# PCB_0014.net
KiCad netlist of a schematic drawn in EAGLE
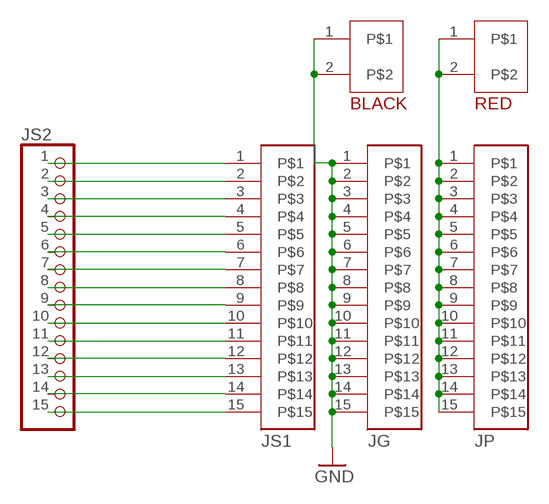
[diagram p0: schematic, sheet 1]

(export (version "E")
  (design (tool "Eeschema 10.0.6"))
  (components
    (comp (ref "BLACK")
      (value "SCREWTERMINAL_2PIN")
      (footprint "eagle-import:DB125-3.5_3.81")
      (libsource (lib "eagle-import") (part "SCREWTERMINAL_2PIN"))
    )
    (comp (ref "JG")
      (value "HEADER_15X1")
      (footprint "eagle-import:HDRV15W64P254_1X15_3810X254X838B")
      (libsource (lib "eagle-import") (part "HEADER_15X1"))
    )
    (comp (ref "JP")
      (value "HEADER_15X1")
      (footprint "eagle-import:HDRV15W64P254_1X15_3810X254X838B")
      (libsource (lib "eagle-import") (part "HEADER_15X1"))
    )
    (comp (ref "JS1")
      (value "HEADER_15X1")
      (footprint "eagle-import:HDRV15W64P254_1X15_3810X254X838B")
      (libsource (lib "eagle-import") (part "HEADER_15X1"))
    )
    (comp (ref "JS2")
      (value "PINHD-1X15")
      (footprint "eagle-import:1X15")
      (libsource (lib "eagle-import") (part "PINHD-1X15"))
    )
    (comp (ref "RED")
      (value "SCREWTERMINAL_2PIN")
      (footprint "eagle-import:DB125-3.5_3.81")
      (libsource (lib "eagle-import") (part "SCREWTERMINAL_2PIN"))
    )
  )
  (nets
    (net (code "1") (name "GND") (class "Default")
      (node (ref "BLACK") (pin "1") (pinfunction "P$1_1") (pintype "bidirectional"))
      (node (ref "BLACK") (pin "2") (pinfunction "P$2_2") (pintype "bidirectional"))
      (node (ref "JG") (pin "1") (pinfunction "P$1_1") (pintype "bidirectional"))
      (node (ref "JG") (pin "10") (pinfunction "P$10_10") (pintype "bidirectional"))
      (node (ref "JG") (pin "11") (pinfunction "P$11_11") (pintype "bidirectional"))
      (node (ref "JG") (pin "12") (pinfunction "P$12_12") (pintype "bidirectional"))
      (node (ref "JG") (pin "13") (pinfunction "P$13_13") (pintype "bidirectional"))
      (node (ref "JG") (pin "14") (pinfunction "P$14_14") (pintype "bidirectional"))
      (node (ref "JG") (pin "15") (pinfunction "P$15_15") (pintype "bidirectional"))
      (node (ref "JG") (pin "2") (pinfunction "P$2_2") (pintype "bidirectional"))
      (node (ref "JG") (pin "3") (pinfunction "P$3_3") (pintype "bidirectional"))
      (node (ref "JG") (pin "4") (pinfunction "P$4_4") (pintype "bidirectional"))
      (node (ref "JG") (pin "5") (pinfunction "P$5_5") (pintype "bidirectional"))
      (node (ref "JG") (pin "6") (pinfunction "P$6_6") (pintype "bidirectional"))
      (node (ref "JG") (pin "7") (pinfunction "P$7_7") (pintype "bidirectional"))
      (node (ref "JG") (pin "8") (pinfunction "P$8_8") (pintype "bidirectional"))
      (node (ref "JG") (pin "9") (pinfunction "P$9_9") (pintype "bidirectional"))
    )
    (net (code "2") (name "Net-(JP-P$1)") (class "Default")
      (node (ref "JP") (pin "1") (pinfunction "P$1_1") (pintype "bidirectional"))
      (node (ref "JP") (pin "10") (pinfunction "P$10_10") (pintype "bidirectional"))
      (node (ref "JP") (pin "11") (pinfunction "P$11_11") (pintype "bidirectional"))
      (node (ref "JP") (pin "12") (pinfunction "P$12_12") (pintype "bidirectional"))
      (node (ref "JP") (pin "13") (pinfunction "P$13_13") (pintype "bidirectional"))
      (node (ref "JP") (pin "14") (pinfunction "P$14_14") (pintype "bidirectional"))
      (node (ref "JP") (pin "15") (pinfunction "P$15_15") (pintype "bidirectional"))
      (node (ref "JP") (pin "2") (pinfunction "P$2_2") (pintype "bidirectional"))
      (node (ref "JP") (pin "3") (pinfunction "P$3_3") (pintype "bidirectional"))
      (node (ref "JP") (pin "4") (pinfunction "P$4_4") (pintype "bidirectional"))
      (node (ref "JP") (pin "5") (pinfunction "P$5_5") (pintype "bidirectional"))
      (node (ref "JP") (pin "6") (pinfunction "P$6_6") (pintype "bidirectional"))
      (node (ref "JP") (pin "7") (pinfunction "P$7_7") (pintype "bidirectional"))
      (node (ref "JP") (pin "8") (pinfunction "P$8_8") (pintype "bidirectional"))
      (node (ref "JP") (pin "9") (pinfunction "P$9_9") (pintype "bidirectional"))
      (node (ref "RED") (pin "1") (pinfunction "P$1_1") (pintype "bidirectional"))
      (node (ref "RED") (pin "2") (pinfunction "P$2_2") (pintype "bidirectional"))
    )
    (net (code "3") (name "Net-(JS1-P$1)") (class "Default")
      (node (ref "JS1") (pin "1") (pinfunction "P$1_1") (pintype "bidirectional"))
      (node (ref "JS2") (pin "1") (pinfunction "1_1") (pintype "passive"))
    )
    (net (code "4") (name "Net-(JS1-P$2)") (class "Default")
      (node (ref "JS1") (pin "2") (pinfunction "P$2_2") (pintype "bidirectional"))
      (node (ref "JS2") (pin "2") (pinfunction "2_2") (pintype "passive"))
    )
    (net (code "5") (name "Net-(JS1-P$3)") (class "Default")
      (node (ref "JS1") (pin "3") (pinfunction "P$3_3") (pintype "bidirectional"))
      (node (ref "JS2") (pin "3") (pinfunction "3_3") (pintype "passive"))
    )
    (net (code "6") (name "Net-(JS1-P$4)") (class "Default")
      (node (ref "JS1") (pin "4") (pinfunction "P$4_4") (pintype "bidirectional"))
      (node (ref "JS2") (pin "4") (pinfunction "4_4") (pintype "passive"))
    )
    (net (code "7") (name "Net-(JS1-P$5)") (class "Default")
      (node (ref "JS1") (pin "5") (pinfunction "P$5_5") (pintype "bidirectional"))
      (node (ref "JS2") (pin "5") (pinfunction "5_5") (pintype "passive"))
    )
    (net (code "8") (name "Net-(JS1-P$6)") (class "Default")
      (node (ref "JS1") (pin "6") (pinfunction "P$6_6") (pintype "bidirectional"))
      (node (ref "JS2") (pin "6") (pinfunction "6_6") (pintype "passive"))
    )
    (net (code "9") (name "Net-(JS1-P$7)") (class "Default")
      (node (ref "JS1") (pin "7") (pinfunction "P$7_7") (pintype "bidirectional"))
      (node (ref "JS2") (pin "7") (pinfunction "7_7") (pintype "passive"))
    )
    (net (code "10") (name "Net-(JS1-P$8)") (class "Default")
      (node (ref "JS1") (pin "8") (pinfunction "P$8_8") (pintype "bidirectional"))
      (node (ref "JS2") (pin "8") (pinfunction "8_8") (pintype "passive"))
    )
    (net (code "11") (name "Net-(JS1-P$9)") (class "Default")
      (node (ref "JS1") (pin "9") (pinfunction "P$9_9") (pintype "bidirectional"))
      (node (ref "JS2") (pin "9") (pinfunction "9_9") (pintype "passive"))
    )
    (net (code "12") (name "Net-(JS1-P$10)") (class "Default")
      (node (ref "JS1") (pin "10") (pinfunction "P$10_10") (pintype "bidirectional"))
      (node (ref "JS2") (pin "10") (pinfunction "10_10") (pintype "passive"))
    )
    (net (code "13") (name "Net-(JS1-P$11)") (class "Default")
      (node (ref "JS1") (pin "11") (pinfunction "P$11_11") (pintype "bidirectional"))
      (node (ref "JS2") (pin "11") (pinfunction "11_11") (pintype "passive"))
    )
    (net (code "14") (name "Net-(JS1-P$12)") (class "Default")
      (node (ref "JS1") (pin "12") (pinfunction "P$12_12") (pintype "bidirectional"))
      (node (ref "JS2") (pin "12") (pinfunction "12_12") (pintype "passive"))
    )
    (net (code "15") (name "Net-(JS1-P$13)") (class "Default")
      (node (ref "JS1") (pin "13") (pinfunction "P$13_13") (pintype "bidirectional"))
      (node (ref "JS2") (pin "13") (pinfunction "13_13") (pintype "passive"))
    )
    (net (code "16") (name "Net-(JS1-P$14)") (class "Default")
      (node (ref "JS1") (pin "14") (pinfunction "P$14_14") (pintype "bidirectional"))
      (node (ref "JS2") (pin "14") (pinfunction "14_14") (pintype "passive"))
    )
    (net (code "17") (name "Net-(JS1-P$15)") (class "Default")
      (node (ref "JS1") (pin "15") (pinfunction "P$15_15") (pintype "bidirectional"))
      (node (ref "JS2") (pin "15") (pinfunction "15_15") (pintype "passive"))
    )
  )
)
